# Sht1_TAUV-Dual_Lipo_Board.net
KiCad netlist of a schematic drawn in Altium Designer
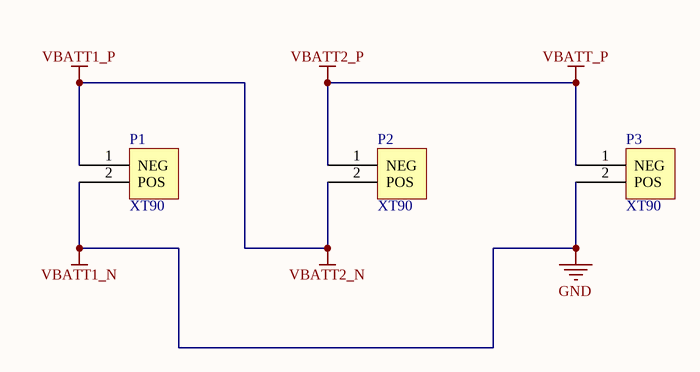
[diagram p0: [Sht1]TAUV-Dual_Lipo_Board.SchDoc]

(export (version "E")
  (design (tool "Eeschema 10.0.6"))
  (components
    (comp (ref "P1") (value "XT90") (footprint "XT90") (libsource (lib "TAUV-Lib") (part "XT90")))
    (comp (ref "P2") (value "XT90") (footprint "XT90") (libsource (lib "TAUV-Lib") (part "XT90")))
    (comp (ref "P3") (value "XT90") (footprint "XT90") (libsource (lib "TAUV-Lib") (part "XT90")))
  )
  (nets
    (net (code "1") (name "GND") (class "Default")
      (node (ref "P1") (pin "2") (pinfunction "POS_2") (pintype "passive"))
      (node (ref "P3") (pin "2") (pinfunction "POS_2") (pintype "passive"))
    )
    (net (code "2") (name "VBATT1_P") (class "Default")
      (node (ref "P1") (pin "1") (pinfunction "NEG_1") (pintype "passive"))
      (node (ref "P2") (pin "2") (pinfunction "POS_2") (pintype "passive"))
    )
    (net (code "3") (name "VBATT2_P") (class "Default")
      (node (ref "P2") (pin "1") (pinfunction "NEG_1") (pintype "passive"))
      (node (ref "P3") (pin "1") (pinfunction "NEG_1") (pintype "passive"))
    )
  )
)
